# CON_USBB_RA.net
KiCad netlist of a schematic drawn in Altium Designer
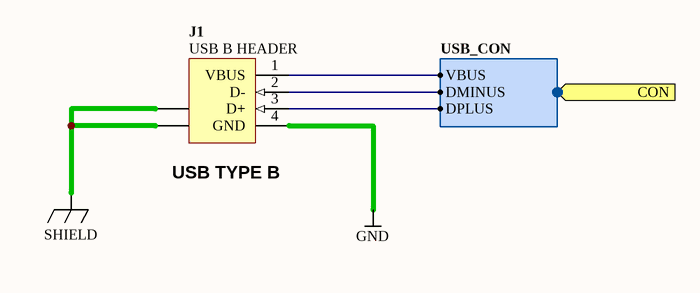
[diagram p0: CON_USBB_RA.SchDoc]

(export (version "E")
  (design (tool "Eeschema 10.0.6"))
  (components
    (comp (ref "J1")
      (value "USB B HEADER")
      (footprint "440119")
      (description "Connector, USB B Type, Right Angle, Thru Hole, White")
      (libsource (lib "altium-import") (part "root_0_mirrored_CON-USBB-6-RA_"))
    )
  )
  (nets
    (net (code "2") (name "/DMINUS") (class "Default")
      (node (ref "J1") (pin "2") (pinfunction "D-_2") (pintype "input"))
    )
    (net (code "3") (name "/DPLUS") (class "Default")
      (node (ref "J1") (pin "3") (pinfunction "D+_3") (pintype "input"))
    )
    (net (code "4") (name "/VBUS") (class "Default")
      (node (ref "J1") (pin "1") (pinfunction "VBUS_1") (pintype "power_in"))
    )
    (net (code "6") (name "GND") (class "Default")
      (node (ref "J1") (pin "4") (pinfunction "GND_4") (pintype "power_in"))
    )
    (net (code "7") (name "SHIELD") (class "Default")
      (node (ref "J1") (pin "5") (pinfunction "SHLD_5") (pintype "passive"))
      (node (ref "J1") (pin "6") (pinfunction "SHLD_6") (pintype "passive"))
    )
  )
)
